# 3_-MCU_MAIN.net
KiCad netlist of a schematic drawn in Altium Designer
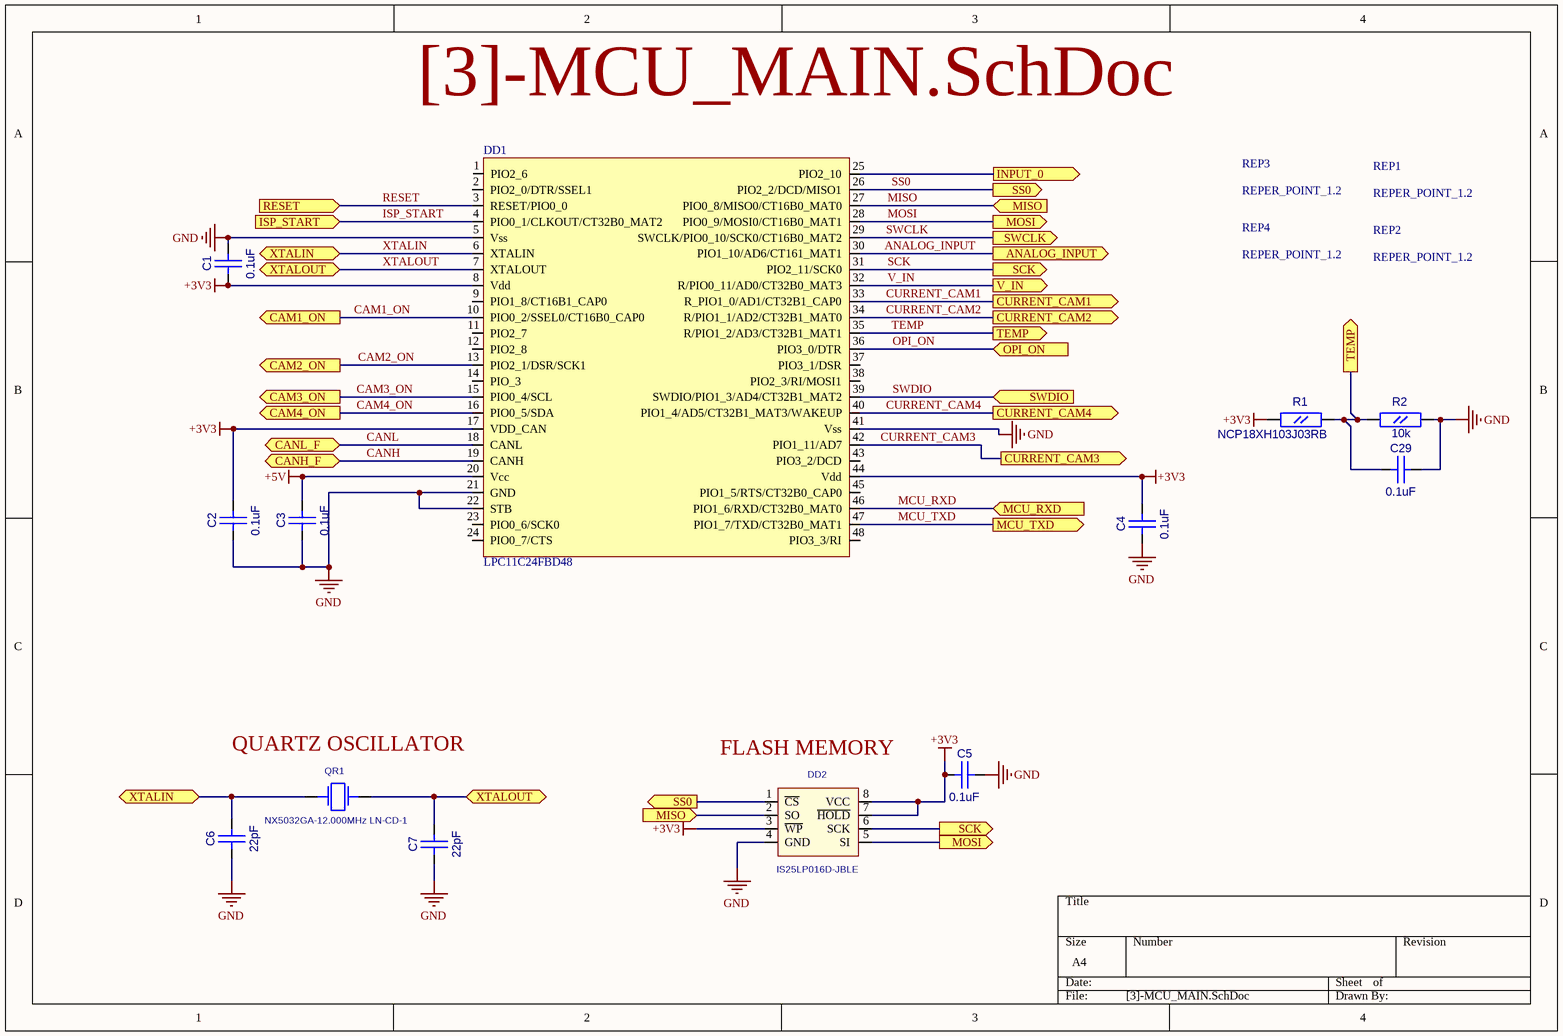
[diagram p0: [3]-MCU_MAIN.SchDoc]

(export (version "E")
  (design (tool "Eeschema 10.0.6"))
  (components
    (comp (ref "C1")
      (value "0.1uF")
      (footprint "CC0603")
      (description "CC0603")
      (libsource (lib "fizik_lib") (part "CC0603"))
    )
    (comp (ref "C2")
      (value "0.1uF")
      (footprint "CC0603")
      (description "CC0603")
      (libsource (lib "fizik_lib") (part "CC0603"))
    )
    (comp (ref "C3")
      (value "0.1uF")
      (footprint "CC0603")
      (description "CC0603")
      (libsource (lib "fizik_lib") (part "CC0603"))
    )
    (comp (ref "C4")
      (value "0.1uF")
      (footprint "CC0603")
      (description "CC0603")
      (libsource (lib "fizik_lib") (part "CC0603"))
    )
    (comp (ref "C5")
      (value "0.1uF")
      (footprint "CC0603")
      (description "CC0603")
      (libsource (lib "gprs_modem_2") (part "CC0603"))
    )
    (comp (ref "C6")
      (value "22pF")
      (footprint "CC0603")
      (description "CC0603")
      (libsource (lib "gprs_modem_2") (part "CC0603"))
    )
    (comp (ref "C7")
      (value "22pF")
      (footprint "CC0603")
      (description "CC0603")
      (libsource (lib "gprs_modem_2") (part "CC0603"))
    )
    (comp (ref "C29")
      (value "0.1uF")
      (footprint "CC0603")
      (description "CC0603")
      (libsource (lib "fizik_lib") (part "CC0603"))
    )
    (comp (ref "DD1")
      (value "LPC11C24FBD48")
      (footprint "LQFP48")
      (libsource (lib "fizik_lib") (part "LPC11C24FBD48"))
    )
    (comp (ref "DD2")
      (value "IS25LP016D-JBLE")
      (footprint "EIAJ_SO8")
      (description "S25FL016A0LMFI01")
      (libsource (lib "gprs_modem_2") (part "S25FL016A0LMFI01"))
    )
    (comp (ref "QR1")
      (value "NX5032GA-12.000MHz LN-CD-1")
      (footprint "AC5032_2")
      (description "AC5032/2")
      (libsource (lib "gprs_modem_2") (part "AC5032_2"))
    )
    (comp (ref "R1")
      (value "NCP18XH103J03RB")
      (footprint "RC0603")
      (description "RC0603")
      (libsource (lib "fizik_lib") (part "RC0603"))
    )
    (comp (ref "R2")
      (value "10k")
      (footprint "RC0603")
      (description "RC0603")
      (libsource (lib "fizik_lib") (part "RC0603"))
    )
    (comp (ref "REP1")
      (value "REPER_POINT_1.2")
      (footprint "REPER1.2")
      (description "REPER1.2")
      (libsource (lib "fizik_lib") (part "REPER1.2"))
    )
    (comp (ref "REP2")
      (value "REPER_POINT_1.2")
      (footprint "REPER1.2")
      (description "REPER1.2")
      (libsource (lib "fizik_lib") (part "REPER1.2"))
    )
    (comp (ref "REP3")
      (value "REPER_POINT_1.2")
      (footprint "REPER1.2")
      (description "REPER1.2")
      (libsource (lib "fizik_lib") (part "REPER1.2"))
    )
    (comp (ref "REP4")
      (value "REPER_POINT_1.2")
      (footprint "REPER1.2")
      (description "REPER1.2")
      (libsource (lib "fizik_lib") (part "REPER1.2"))
    )
  )
  (nets
    (net (code "1") (name "+3V3") (class "Default")
      (node (ref "C1") (pin "1") (pinfunction "A_1") (pintype "passive"))
      (node (ref "C2") (pin "2") (pinfunction "B_2") (pintype "passive"))
      (node (ref "C4") (pin "2") (pinfunction "B_2") (pintype "passive"))
      (node (ref "C5") (pin "1") (pinfunction "A_1") (pintype "passive"))
      (node (ref "DD1") (pin "17") (pinfunction "VDD_CAN_17") (pintype "passive"))
      (node (ref "DD1") (pin "44") (pinfunction "Vdd_44") (pintype "passive"))
      (node (ref "DD1") (pin "8") (pinfunction "Vdd_8") (pintype "passive"))
      (node (ref "DD2") (pin "3") (pinfunction "~{WP}_3") (pintype "passive"))
      (node (ref "DD2") (pin "7") (pinfunction "~{HOLD}_7") (pintype "passive"))
      (node (ref "DD2") (pin "8") (pinfunction "VCC_8") (pintype "passive"))
      (node (ref "R1") (pin "1") (pinfunction "A_1") (pintype "passive"))
    )
    (net (code "2") (name "+5V") (class "Default")
      (node (ref "C3") (pin "2") (pinfunction "B_2") (pintype "passive"))
      (node (ref "DD1") (pin "20") (pinfunction "Vcc_20") (pintype "passive"))
    )
    (net (code "3") (name "/ANALOG_INPUT") (class "Default")
      (node (ref "DD1") (pin "30") (pinfunction "PIO1_10/AD6/CT161_MAT1_30") (pintype "passive"))
    )
    (net (code "4") (name "/CAM1_ON") (class "Default")
      (node (ref "DD1") (pin "10") (pinfunction "PIO0_2/SSEL0/CT16B0_CAP0_10") (pintype "passive"))
    )
    (net (code "5") (name "/CAM2_ON") (class "Default")
      (node (ref "DD1") (pin "13") (pinfunction "PIO2_1/DSR/SCK1_13") (pintype "passive"))
    )
    (net (code "6") (name "/CAM3_ON") (class "Default")
      (node (ref "DD1") (pin "15") (pinfunction "PIO0_4/SCL_15") (pintype "passive"))
    )
    (net (code "7") (name "/CAM4_ON") (class "Default")
      (node (ref "DD1") (pin "16") (pinfunction "PIO0_5/SDA_16") (pintype "passive"))
    )
    (net (code "8") (name "/CANH") (class "Default")
      (node (ref "DD1") (pin "19") (pinfunction "CANH_19") (pintype "passive"))
    )
    (net (code "9") (name "/CANL") (class "Default")
      (node (ref "DD1") (pin "18") (pinfunction "CANL_18") (pintype "passive"))
    )
    (net (code "10") (name "/CURRENT_CAM1") (class "Default")
      (node (ref "DD1") (pin "33") (pinfunction "R_PIO1_0/AD1/CT32B1_CAP0_33") (pintype "passive"))
    )
    (net (code "11") (name "/CURRENT_CAM2") (class "Default")
      (node (ref "DD1") (pin "34") (pinfunction "R/PIO1_1/AD2/CT32B1_MAT0_34") (pintype "passive"))
    )
    (net (code "12") (name "/CURRENT_CAM3") (class "Default")
      (node (ref "DD1") (pin "42") (pinfunction "PIO1_11/AD7_42") (pintype "passive"))
    )
    (net (code "13") (name "/CURRENT_CAM4") (class "Default")
      (node (ref "DD1") (pin "40") (pinfunction "PIO1_4/AD5/CT32B1_MAT3/WAKEUP_40") (pintype "passive"))
    )
    (net (code "14") (name "/INPUT_0") (class "Default")
      (node (ref "DD1") (pin "25") (pinfunction "PIO2_10_25") (pintype "passive"))
    )
    (net (code "15") (name "/ISP_START") (class "Default")
      (node (ref "DD1") (pin "4") (pinfunction "PIO0_1/CLKOUT/CT32B0_MAT2_4") (pintype "passive"))
    )
    (net (code "16") (name "/MCU_RXD") (class "Default")
      (node (ref "DD1") (pin "46") (pinfunction "PIO1_6/RXD/CT32B0_MAT0_46") (pintype "passive"))
    )
    (net (code "17") (name "/MCU_TXD") (class "Default")
      (node (ref "DD1") (pin "47") (pinfunction "PIO1_7/TXD/CT32B0_MAT1_47") (pintype "passive"))
    )
    (net (code "18") (name "/MISO") (class "Default")
      (node (ref "DD1") (pin "27") (pinfunction "PIO0_8/MISO0/CT16B0_MAT0_27") (pintype "passive"))
      (node (ref "DD2") (pin "2") (pinfunction "SO_2") (pintype "passive"))
    )
    (net (code "19") (name "/MOSI") (class "Default")
      (node (ref "DD1") (pin "28") (pinfunction "PIO0_9/MOSI0/CT16B0_MAT1_28") (pintype "passive"))
      (node (ref "DD2") (pin "5") (pinfunction "SI_5") (pintype "passive"))
    )
    (net (code "20") (name "/OPI_ON") (class "Default")
      (node (ref "DD1") (pin "36") (pinfunction "PIO3_0/DTR_36") (pintype "passive"))
    )
    (net (code "21") (name "/RESET") (class "Default")
      (node (ref "DD1") (pin "3") (pinfunction "RESET/PIO0_0_3") (pintype "passive"))
    )
    (net (code "22") (name "/SCK") (class "Default")
      (node (ref "DD1") (pin "31") (pinfunction "PIO2_11/SCK0_31") (pintype "passive"))
      (node (ref "DD2") (pin "6") (pinfunction "SCK_6") (pintype "passive"))
    )
    (net (code "23") (name "/SS0") (class "Default")
      (node (ref "DD1") (pin "26") (pinfunction "PIO2_2/DCD/MISO1_26") (pintype "passive"))
      (node (ref "DD2") (pin "1") (pinfunction "~{CS}_1") (pintype "passive"))
    )
    (net (code "24") (name "/SWCLK") (class "Default")
      (node (ref "DD1") (pin "29") (pinfunction "SWCLK/PIO0_10/SCK0/CT16B0_MAT2_29") (pintype "passive"))
    )
    (net (code "25") (name "/SWDIO") (class "Default")
      (node (ref "DD1") (pin "39") (pinfunction "SWDIO/PIO1_3/AD4/CT32B1_MAT2_39") (pintype "passive"))
    )
    (net (code "26") (name "/TEMP") (class "Default")
      (node (ref "C29") (pin "1") (pinfunction "A_1") (pintype "passive"))
      (node (ref "DD1") (pin "35") (pinfunction "R/PIO1_2/AD3/CT32B1_MAT1_35") (pintype "passive"))
      (node (ref "R1") (pin "2") (pinfunction "B_2") (pintype "passive"))
      (node (ref "R2") (pin "1") (pinfunction "A_1") (pintype "passive"))
    )
    (net (code "27") (name "/V_IN") (class "Default")
      (node (ref "DD1") (pin "32") (pinfunction "R/PIO0_11/AD0/CT32B0_MAT3_32") (pintype "passive"))
    )
    (net (code "28") (name "/XTALIN") (class "Default")
      (node (ref "C6") (pin "2") (pinfunction "B_2") (pintype "passive"))
      (node (ref "DD1") (pin "6") (pinfunction "XTALIN_6") (pintype "passive"))
      (node (ref "QR1") (pin "1") (pintype "passive"))
    )
    (net (code "29") (name "/XTALOUT") (class "Default")
      (node (ref "C7") (pin "2") (pinfunction "B_2") (pintype "passive"))
      (node (ref "DD1") (pin "7") (pinfunction "XTALOUT_7") (pintype "passive"))
      (node (ref "QR1") (pin "2") (pintype "passive"))
    )
    (net (code "30") (name "GND") (class "Default")
      (node (ref "C1") (pin "2") (pinfunction "B_2") (pintype "passive"))
      (node (ref "C2") (pin "1") (pinfunction "A_1") (pintype "passive"))
      (node (ref "C29") (pin "2") (pinfunction "B_2") (pintype "passive"))
      (node (ref "C3") (pin "1") (pinfunction "A_1") (pintype "passive"))
      (node (ref "C4") (pin "1") (pinfunction "A_1") (pintype "passive"))
      (node (ref "C5") (pin "2") (pinfunction "B_2") (pintype "passive"))
      (node (ref "C6") (pin "1") (pinfunction "A_1") (pintype "passive"))
      (node (ref "C7") (pin "1") (pinfunction "A_1") (pintype "passive"))
      (node (ref "DD1") (pin "21") (pinfunction "GND_21") (pintype "passive"))
      (node (ref "DD1") (pin "22") (pinfunction "STB_22") (pintype "passive"))
      (node (ref "DD1") (pin "41") (pinfunction "Vss_41") (pintype "passive"))
      (node (ref "DD1") (pin "5") (pinfunction "Vss_5") (pintype "passive"))
      (node (ref "DD2") (pin "4") (pinfunction "GND_4") (pintype "passive"))
      (node (ref "R2") (pin "2") (pinfunction "B_2") (pintype "passive"))
    )
    (net (code "31") (name "unconnected-(DD1-PIO0_6{slash}SCK0-Pad23)") (class "Default")
      (node (ref "DD1") (pin "23") (pinfunction "PIO0_6/SCK0_23") (pintype "passive"))
    )
    (net (code "32") (name "unconnected-(DD1-PIO0_7{slash}CTS-Pad24)") (class "Default")
      (node (ref "DD1") (pin "24") (pinfunction "PIO0_7/CTS_24") (pintype "passive"))
    )
    (net (code "33") (name "unconnected-(DD1-PIO1_5{slash}RTS{slash}CT32B0_CAP0-Pad45)") (class "Default")
      (node (ref "DD1") (pin "45") (pinfunction "PIO1_5/RTS/CT32B0_CAP0_45") (pintype "passive"))
    )
    (net (code "34") (name "unconnected-(DD1-PIO1_8{slash}CT16B1_CAP0-Pad9)") (class "Default")
      (node (ref "DD1") (pin "9") (pinfunction "PIO1_8/CT16B1_CAP0_9") (pintype "passive"))
    )
    (net (code "35") (name "unconnected-(DD1-PIO2_0{slash}DTR{slash}SSEL1-Pad2)") (class "Default")
      (node (ref "DD1") (pin "2") (pinfunction "PIO2_0/DTR/SSEL1_2") (pintype "passive"))
    )
    (net (code "36") (name "unconnected-(DD1-PIO2_3{slash}RI{slash}MOSI1-Pad38)") (class "Default")
      (node (ref "DD1") (pin "38") (pinfunction "PIO2_3/RI/MOSI1_38") (pintype "passive"))
    )
    (net (code "37") (name "unconnected-(DD1-PIO2_6-Pad1)") (class "Default")
      (node (ref "DD1") (pin "1") (pinfunction "PIO2_6_1") (pintype "passive"))
    )
    (net (code "38") (name "unconnected-(DD1-PIO2_7-Pad11)") (class "Default")
      (node (ref "DD1") (pin "11") (pinfunction "PIO2_7_11") (pintype "passive"))
    )
    (net (code "39") (name "unconnected-(DD1-PIO2_8-Pad12)") (class "Default")
      (node (ref "DD1") (pin "12") (pinfunction "PIO2_8_12") (pintype "passive"))
    )
    (net (code "40") (name "unconnected-(DD1-PIO3_1{slash}DSR-Pad37)") (class "Default")
      (node (ref "DD1") (pin "37") (pinfunction "PIO3_1/DSR_37") (pintype "passive"))
    )
    (net (code "41") (name "unconnected-(DD1-PIO3_2{slash}DCD-Pad43)") (class "Default")
      (node (ref "DD1") (pin "43") (pinfunction "PIO3_2/DCD_43") (pintype "passive"))
    )
    (net (code "42") (name "unconnected-(DD1-PIO3_3{slash}RI-Pad48)") (class "Default")
      (node (ref "DD1") (pin "48") (pinfunction "PIO3_3/RI_48") (pintype "passive"))
    )
    (net (code "43") (name "unconnected-(DD1-PIO_3-Pad14)") (class "Default")
      (node (ref "DD1") (pin "14") (pinfunction "PIO_3_14") (pintype "passive"))
    )
    (net (code "44") (name "unconnected-(REP1-Pad1)") (class "Default")
      (node (ref "REP1") (pin "1") (pintype "passive"))
    )
    (net (code "45") (name "unconnected-(REP2-Pad1)") (class "Default")
      (node (ref "REP2") (pin "1") (pintype "passive"))
    )
    (net (code "46") (name "unconnected-(REP3-Pad1)") (class "Default")
      (node (ref "REP3") (pin "1") (pintype "passive"))
    )
    (net (code "47") (name "unconnected-(REP4-Pad1)") (class "Default")
      (node (ref "REP4") (pin "1") (pintype "passive"))
    )
  )
)
